# Display-Board_Rack-PDU_3_0.net
KiCad netlist of a schematic drawn in EAGLE
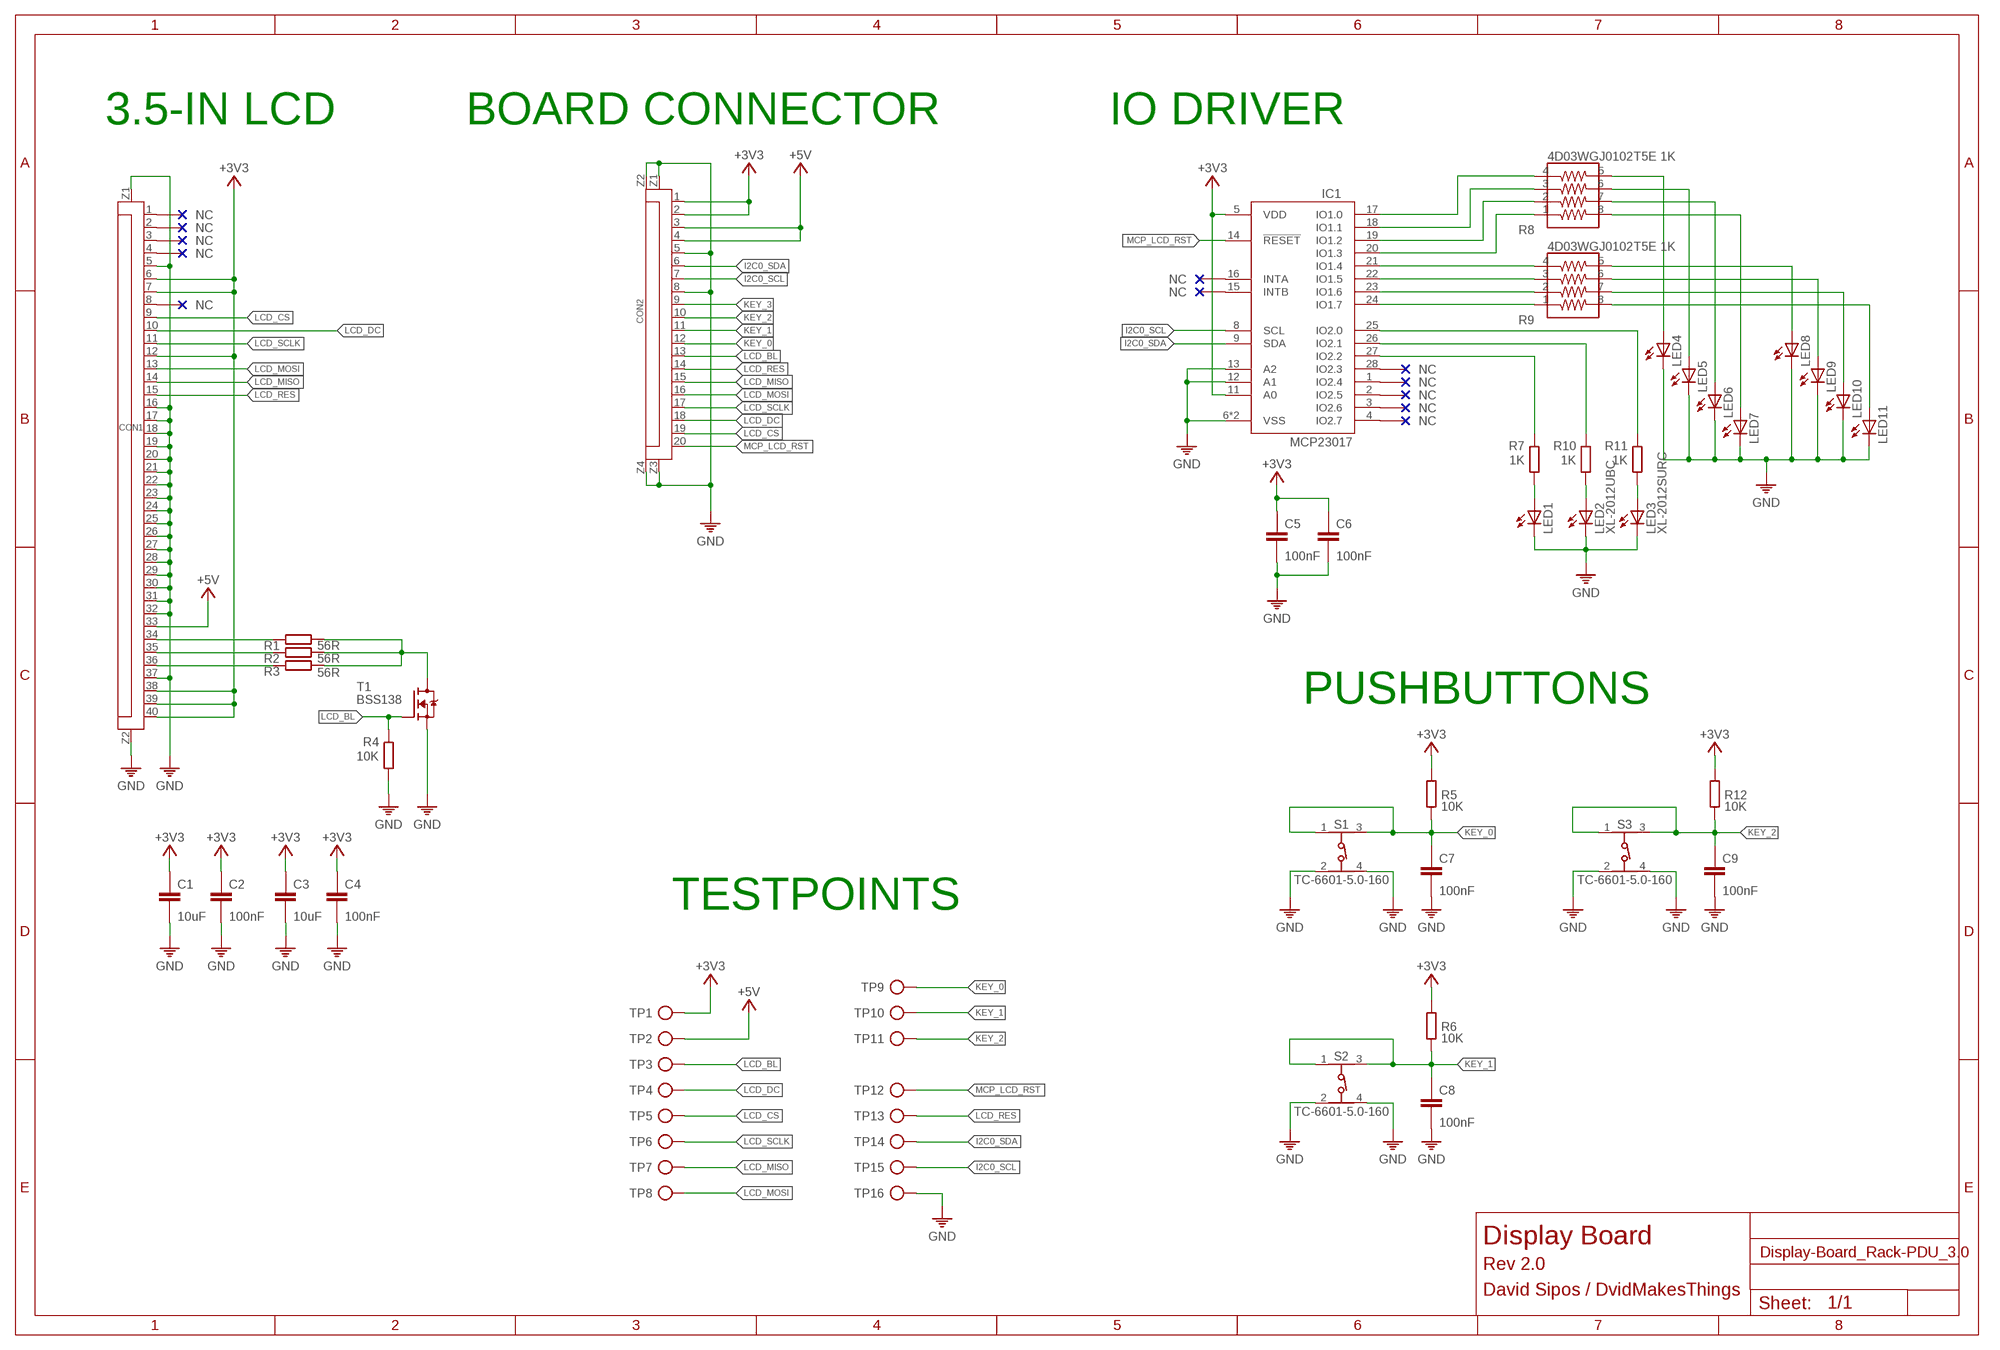
[diagram p0: schematic, sheet 1]

(export (version "E")
  (design (tool "Eeschema 10.0.6"))
  (components
    (comp (ref "C1")
      (value "10uF")
      (footprint "eagle-import:C0402")
      (libsource (lib "eagle-import") (part "C-0402"))
    )
    (comp (ref "C2")
      (value "100nF")
      (footprint "eagle-import:C0402")
      (libsource (lib "eagle-import") (part "C-0402"))
    )
    (comp (ref "C3")
      (value "10uF")
      (footprint "eagle-import:C0402")
      (libsource (lib "eagle-import") (part "C-0402"))
    )
    (comp (ref "C4")
      (value "100nF")
      (footprint "eagle-import:C0402")
      (libsource (lib "eagle-import") (part "C-0402"))
    )
    (comp (ref "C5")
      (value "100nF")
      (footprint "eagle-import:C0402")
      (libsource (lib "eagle-import") (part "C-0402"))
    )
    (comp (ref "C6")
      (value "100nF")
      (footprint "eagle-import:C0402")
      (libsource (lib "eagle-import") (part "C-0402"))
    )
    (comp (ref "C7")
      (value "100nF")
      (footprint "eagle-import:C0402")
      (libsource (lib "eagle-import") (part "C-0402"))
    )
    (comp (ref "C8")
      (value "100nF")
      (footprint "eagle-import:C0402")
      (libsource (lib "eagle-import") (part "C-0402"))
    )
    (comp (ref "C9")
      (value "100nF")
      (footprint "eagle-import:C0402")
      (libsource (lib "eagle-import") (part "C-0402"))
    )
    (comp (ref "CON1")
      (value "FPC40-HD")
      (footprint "eagle-import:FPC40_3.5TFT")
      (libsource (lib "eagle-import") (part "FPC40-HD"))
    )
    (comp (ref "CON2")
      (value "FPC20-H")
      (footprint "eagle-import:FPC20")
      (libsource (lib "eagle-import") (part "FPC20-H"))
    )
    (comp (ref "IC1")
      (value "MCP23017-E/ML")
      (footprint "eagle-import:QFN28[6X6]ML")
      (libsource (lib "eagle-import") (part "MCP23017-E/ML"))
    )
    (comp (ref "LED1")
      (value "LEDCHIP-LED0805")
      (footprint "eagle-import:CHIP-LED0805")
      (libsource (lib "eagle-import") (part "LEDCHIP-LED0805"))
    )
    (comp (ref "LED2")
      (value "XL-2012UBC")
      (footprint "eagle-import:CHIP-LED0805")
      (libsource (lib "eagle-import") (part "LEDCHIP-LED0805"))
    )
    (comp (ref "LED3")
      (value "XL-2012SURC")
      (footprint "eagle-import:CHIP-LED0805")
      (libsource (lib "eagle-import") (part "LEDCHIP-LED0805"))
    )
    (comp (ref "LED4")
      (value "LEDCHIP-LED0805")
      (footprint "eagle-import:CHIP-LED0805")
      (libsource (lib "eagle-import") (part "LEDCHIP-LED0805"))
    )
    (comp (ref "LED5")
      (value "LEDCHIP-LED0805")
      (footprint "eagle-import:CHIP-LED0805")
      (libsource (lib "eagle-import") (part "LEDCHIP-LED0805"))
    )
    (comp (ref "LED6")
      (value "LEDCHIP-LED0805")
      (footprint "eagle-import:CHIP-LED0805")
      (libsource (lib "eagle-import") (part "LEDCHIP-LED0805"))
    )
    (comp (ref "LED7")
      (value "LEDCHIP-LED0805")
      (footprint "eagle-import:CHIP-LED0805")
      (libsource (lib "eagle-import") (part "LEDCHIP-LED0805"))
    )
    (comp (ref "LED8")
      (value "LEDCHIP-LED0805")
      (footprint "eagle-import:CHIP-LED0805")
      (libsource (lib "eagle-import") (part "LEDCHIP-LED0805"))
    )
    (comp (ref "LED9")
      (value "LEDCHIP-LED0805")
      (footprint "eagle-import:CHIP-LED0805")
      (libsource (lib "eagle-import") (part "LEDCHIP-LED0805"))
    )
    (comp (ref "LED10")
      (value "LEDCHIP-LED0805")
      (footprint "eagle-import:CHIP-LED0805")
      (libsource (lib "eagle-import") (part "LEDCHIP-LED0805"))
    )
    (comp (ref "LED11")
      (value "LEDCHIP-LED0805")
      (footprint "eagle-import:CHIP-LED0805")
      (libsource (lib "eagle-import") (part "LEDCHIP-LED0805"))
    )
    (comp (ref "R1")
      (value "56R")
      (footprint "eagle-import:0402")
      (libsource (lib "eagle-import") (part "R0402"))
    )
    (comp (ref "R2")
      (value "56R")
      (footprint "eagle-import:0402")
      (libsource (lib "eagle-import") (part "R0402"))
    )
    (comp (ref "R3")
      (value "56R")
      (footprint "eagle-import:0402")
      (libsource (lib "eagle-import") (part "R0402"))
    )
    (comp (ref "R4")
      (value "10K")
      (footprint "eagle-import:0402")
      (libsource (lib "eagle-import") (part "R0402"))
    )
    (comp (ref "R5")
      (value "10K")
      (footprint "eagle-import:0402")
      (libsource (lib "eagle-import") (part "R0402"))
    )
    (comp (ref "R6")
      (value "10K")
      (footprint "eagle-import:0402")
      (libsource (lib "eagle-import") (part "R0402"))
    )
    (comp (ref "R7")
      (value "1K")
      (footprint "eagle-import:0402")
      (libsource (lib "eagle-import") (part "R0402"))
    )
    (comp (ref "R8")
      (value "4D03WGJ0102T5E 1K")
      (footprint "eagle-import:742C083103JP")
      (fields
        (field (name "MANUFACTURER") "CTS Resistor Products")
        (field (name "MPN") "742C083103JP")
        (field (name "CREATED_BY") "PCBLayout.com")
      )
      (libsource (lib "eagle-import") (part "742C083103JP"))
    )
    (comp (ref "R9")
      (value "4D03WGJ0102T5E 1K")
      (footprint "eagle-import:742C083103JP")
      (fields
        (field (name "MANUFACTURER") "CTS Resistor Products")
        (field (name "MPN") "742C083103JP")
        (field (name "CREATED_BY") "PCBLayout.com")
      )
      (libsource (lib "eagle-import") (part "742C083103JP"))
    )
    (comp (ref "R10")
      (value "1K")
      (footprint "eagle-import:0402")
      (libsource (lib "eagle-import") (part "R0402"))
    )
    (comp (ref "R11")
      (value "1K")
      (footprint "eagle-import:0402")
      (libsource (lib "eagle-import") (part "R0402"))
    )
    (comp (ref "R12")
      (value "10K")
      (footprint "eagle-import:0402")
      (libsource (lib "eagle-import") (part "R0402"))
    )
    (comp (ref "S1")
      (value "TC-6601-5.0-160")
      (footprint "eagle-import:430182043816")
      (libsource (lib "eagle-import") (part "430182043816"))
    )
    (comp (ref "S2")
      (value "TC-6601-5.0-160")
      (footprint "eagle-import:430182043816")
      (libsource (lib "eagle-import") (part "430182043816"))
    )
    (comp (ref "S3")
      (value "TC-6601-5.0-160")
      (footprint "eagle-import:430182043816")
      (libsource (lib "eagle-import") (part "430182043816"))
    )
    (comp (ref "T1")
      (value "BSS138")
      (footprint "eagle-import:SOT23")
      (libsource (lib "eagle-import") (part "BSS138"))
    )
    (comp (ref "TP1") (value "TP") (footprint "eagle-import:TP") (libsource (lib "eagle-import") (part "TP")))
    (comp (ref "TP2") (value "TP") (footprint "eagle-import:TP") (libsource (lib "eagle-import") (part "TP")))
    (comp (ref "TP3") (value "TP") (footprint "eagle-import:TP") (libsource (lib "eagle-import") (part "TP")))
    (comp (ref "TP4") (value "TP") (footprint "eagle-import:TP") (libsource (lib "eagle-import") (part "TP")))
    (comp (ref "TP5") (value "TP") (footprint "eagle-import:TP") (libsource (lib "eagle-import") (part "TP")))
    (comp (ref "TP6") (value "TP") (footprint "eagle-import:TP") (libsource (lib "eagle-import") (part "TP")))
    (comp (ref "TP7") (value "TP") (footprint "eagle-import:TP") (libsource (lib "eagle-import") (part "TP")))
    (comp (ref "TP8") (value "TP") (footprint "eagle-import:TP") (libsource (lib "eagle-import") (part "TP")))
    (comp (ref "TP9") (value "TP") (footprint "eagle-import:TP") (libsource (lib "eagle-import") (part "TP")))
    (comp (ref "TP10")
      (value "TP")
      (footprint "eagle-import:TP")
      (libsource (lib "eagle-import") (part "TP"))
    )
    (comp (ref "TP11")
      (value "TP")
      (footprint "eagle-import:TP")
      (libsource (lib "eagle-import") (part "TP"))
    )
    (comp (ref "TP12")
      (value "TP")
      (footprint "eagle-import:TP")
      (libsource (lib "eagle-import") (part "TP"))
    )
    (comp (ref "TP13")
      (value "TP")
      (footprint "eagle-import:TP")
      (libsource (lib "eagle-import") (part "TP"))
    )
    (comp (ref "TP14")
      (value "TP")
      (footprint "eagle-import:TP")
      (libsource (lib "eagle-import") (part "TP"))
    )
    (comp (ref "TP15")
      (value "TP")
      (footprint "eagle-import:TP")
      (libsource (lib "eagle-import") (part "TP"))
    )
    (comp (ref "TP16")
      (value "TP")
      (footprint "eagle-import:TP")
      (libsource (lib "eagle-import") (part "TP"))
    )
  )
  (nets
    (net (code "1") (name "+3V3") (class "Default")
      (node (ref "C1") (pin "1") (pinfunction "1_1") (pintype "passive"))
      (node (ref "C2") (pin "1") (pinfunction "1_1") (pintype "passive"))
      (node (ref "C3") (pin "1") (pinfunction "1_1") (pintype "passive"))
      (node (ref "C4") (pin "1") (pinfunction "1_1") (pintype "passive"))
      (node (ref "C5") (pin "1") (pinfunction "1_1") (pintype "passive"))
      (node (ref "C6") (pin "1") (pinfunction "1_1") (pintype "passive"))
      (node (ref "CON1") (pin "12") (pinfunction "12_12") (pintype "bidirectional"))
      (node (ref "CON1") (pin "38") (pinfunction "38_38") (pintype "bidirectional"))
      (node (ref "CON1") (pin "39") (pinfunction "39_39") (pintype "bidirectional"))
      (node (ref "CON1") (pin "40") (pinfunction "40_40") (pintype "bidirectional"))
      (node (ref "CON1") (pin "6") (pinfunction "6_6") (pintype "bidirectional"))
      (node (ref "CON1") (pin "7") (pinfunction "7_7") (pintype "bidirectional"))
      (node (ref "CON2") (pin "1") (pinfunction "1_1") (pintype "bidirectional"))
      (node (ref "CON2") (pin "2") (pinfunction "2_2") (pintype "bidirectional"))
      (node (ref "IC1") (pin "11") (pinfunction "A0_11") (pintype "bidirectional"))
      (node (ref "IC1") (pin "5") (pinfunction "VDD_5") (pintype "bidirectional"))
      (node (ref "R12") (pin "1") (pinfunction "1_1") (pintype "passive"))
      (node (ref "R5") (pin "1") (pinfunction "1_1") (pintype "passive"))
      (node (ref "R6") (pin "1") (pinfunction "1_1") (pintype "passive"))
      (node (ref "TP1") (pin "TP") (pinfunction "P$1_TP") (pintype "bidirectional"))
    )
    (net (code "2") (name "+5V") (class "Default")
      (node (ref "CON1") (pin "33") (pinfunction "33_33") (pintype "bidirectional"))
      (node (ref "CON2") (pin "3") (pinfunction "3_3") (pintype "bidirectional"))
      (node (ref "CON2") (pin "4") (pinfunction "4_4") (pintype "bidirectional"))
      (node (ref "TP2") (pin "TP") (pinfunction "P$1_TP") (pintype "bidirectional"))
    )
    (net (code "3") (name "GND") (class "Default")
      (node (ref "C1") (pin "2") (pinfunction "2_2") (pintype "passive"))
      (node (ref "C2") (pin "2") (pinfunction "2_2") (pintype "passive"))
      (node (ref "C3") (pin "2") (pinfunction "2_2") (pintype "passive"))
      (node (ref "C4") (pin "2") (pinfunction "2_2") (pintype "passive"))
      (node (ref "C5") (pin "2") (pinfunction "2_2") (pintype "passive"))
      (node (ref "C6") (pin "2") (pinfunction "2_2") (pintype "passive"))
      (node (ref "C7") (pin "2") (pinfunction "2_2") (pintype "passive"))
      (node (ref "C8") (pin "2") (pinfunction "2_2") (pintype "passive"))
      (node (ref "C9") (pin "2") (pinfunction "2_2") (pintype "passive"))
      (node (ref "CON1") (pin "16") (pinfunction "16_16") (pintype "bidirectional"))
      (node (ref "CON1") (pin "17") (pinfunction "17_17") (pintype "bidirectional"))
      (node (ref "CON1") (pin "18") (pinfunction "18_18") (pintype "bidirectional"))
      (node (ref "CON1") (pin "19") (pinfunction "19_19") (pintype "bidirectional"))
      (node (ref "CON1") (pin "20") (pinfunction "20_20") (pintype "bidirectional"))
      (node (ref "CON1") (pin "21") (pinfunction "21_21") (pintype "bidirectional"))
      (node (ref "CON1") (pin "22") (pinfunction "22_22") (pintype "bidirectional"))
      (node (ref "CON1") (pin "23") (pinfunction "23_23") (pintype "bidirectional"))
      (node (ref "CON1") (pin "24") (pinfunction "24_24") (pintype "bidirectional"))
      (node (ref "CON1") (pin "25") (pinfunction "25_25") (pintype "bidirectional"))
      (node (ref "CON1") (pin "26") (pinfunction "26_26") (pintype "bidirectional"))
      (node (ref "CON1") (pin "27") (pinfunction "27_27") (pintype "bidirectional"))
      (node (ref "CON1") (pin "28") (pinfunction "28_28") (pintype "bidirectional"))
      (node (ref "CON1") (pin "29") (pinfunction "29_29") (pintype "bidirectional"))
      (node (ref "CON1") (pin "30") (pinfunction "30_30") (pintype "bidirectional"))
      (node (ref "CON1") (pin "31") (pinfunction "31_31") (pintype "bidirectional"))
      (node (ref "CON1") (pin "32") (pinfunction "32_32") (pintype "bidirectional"))
      (node (ref "CON1") (pin "37") (pinfunction "37_37") (pintype "bidirectional"))
      (node (ref "CON1") (pin "5") (pinfunction "5_5") (pintype "bidirectional"))
      (node (ref "CON1") (pin "Z1") (pinfunction "Z1_Z1") (pintype "bidirectional"))
      (node (ref "CON1") (pin "Z2") (pinfunction "Z2_Z2") (pintype "bidirectional"))
      (node (ref "CON2") (pin "5") (pinfunction "5_5") (pintype "bidirectional"))
      (node (ref "CON2") (pin "8") (pinfunction "8_8") (pintype "bidirectional"))
      (node (ref "CON2") (pin "Z1") (pinfunction "Z1_Z1") (pintype "bidirectional"))
      (node (ref "CON2") (pin "Z2") (pinfunction "Z2_Z2") (pintype "bidirectional"))
      (node (ref "CON2") (pin "Z3") (pinfunction "Z3_Z3") (pintype "bidirectional"))
      (node (ref "CON2") (pin "Z4") (pinfunction "Z4_Z4") (pintype "bidirectional"))
      (node (ref "IC1") (pin "12") (pinfunction "A1_12") (pintype "bidirectional"))
      (node (ref "IC1") (pin "13") (pinfunction "A2_13") (pintype "bidirectional"))
      (node (ref "IC1") (pin "6") (pinfunction "VSS_6") (pintype "bidirectional"))
      (node (ref "IC1") (pin "PAD") (pinfunction "VSS_PAD") (pintype "bidirectional"))
      (node (ref "LED1") (pin "C") (pinfunction "C_C") (pintype "passive"))
      (node (ref "LED10") (pin "C") (pinfunction "C_C") (pintype "passive"))
      (node (ref "LED11") (pin "C") (pinfunction "C_C") (pintype "passive"))
      (node (ref "LED2") (pin "C") (pinfunction "C_C") (pintype "passive"))
      (node (ref "LED3") (pin "C") (pinfunction "C_C") (pintype "passive"))
      (node (ref "LED4") (pin "C") (pinfunction "C_C") (pintype "passive"))
      (node (ref "LED5") (pin "C") (pinfunction "C_C") (pintype "passive"))
      (node (ref "LED6") (pin "C") (pinfunction "C_C") (pintype "passive"))
      (node (ref "LED7") (pin "C") (pinfunction "C_C") (pintype "passive"))
      (node (ref "LED8") (pin "C") (pinfunction "C_C") (pintype "passive"))
      (node (ref "LED9") (pin "C") (pinfunction "C_C") (pintype "passive"))
      (node (ref "R4") (pin "2") (pinfunction "2_2") (pintype "passive"))
      (node (ref "S1") (pin "2") (pinfunction "2_2") (pintype "passive"))
      (node (ref "S1") (pin "4") (pinfunction "4_4") (pintype "passive"))
      (node (ref "S2") (pin "2") (pinfunction "2_2") (pintype "passive"))
      (node (ref "S2") (pin "4") (pinfunction "4_4") (pintype "passive"))
      (node (ref "S3") (pin "2") (pinfunction "2_2") (pintype "passive"))
      (node (ref "S3") (pin "4") (pinfunction "4_4") (pintype "passive"))
      (node (ref "T1") (pin "2") (pinfunction "S_2") (pintype "passive"))
      (node (ref "TP16") (pin "TP") (pinfunction "P$1_TP") (pintype "bidirectional"))
    )
    (net (code "4") (name "I2C0_SCL") (class "Default")
      (node (ref "CON2") (pin "7") (pinfunction "7_7") (pintype "bidirectional"))
      (node (ref "IC1") (pin "8") (pinfunction "SCL_8") (pintype "bidirectional"))
      (node (ref "TP15") (pin "TP") (pinfunction "P$1_TP") (pintype "bidirectional"))
    )
    (net (code "5") (name "I2C0_SDA") (class "Default")
      (node (ref "CON2") (pin "6") (pinfunction "6_6") (pintype "bidirectional"))
      (node (ref "IC1") (pin "9") (pinfunction "SDA_9") (pintype "bidirectional"))
      (node (ref "TP14") (pin "TP") (pinfunction "P$1_TP") (pintype "bidirectional"))
    )
    (net (code "6") (name "KEY_0") (class "Default")
      (node (ref "C7") (pin "1") (pinfunction "1_1") (pintype "passive"))
      (node (ref "CON2") (pin "12") (pinfunction "12_12") (pintype "bidirectional"))
      (node (ref "R5") (pin "2") (pinfunction "2_2") (pintype "passive"))
      (node (ref "S1") (pin "1") (pinfunction "1_1") (pintype "passive"))
      (node (ref "S1") (pin "3") (pinfunction "3_3") (pintype "passive"))
      (node (ref "TP9") (pin "TP") (pinfunction "P$1_TP") (pintype "bidirectional"))
    )
    (net (code "7") (name "KEY_1") (class "Default")
      (node (ref "C8") (pin "1") (pinfunction "1_1") (pintype "passive"))
      (node (ref "CON2") (pin "11") (pinfunction "11_11") (pintype "bidirectional"))
      (node (ref "R6") (pin "2") (pinfunction "2_2") (pintype "passive"))
      (node (ref "S2") (pin "1") (pinfunction "1_1") (pintype "passive"))
      (node (ref "S2") (pin "3") (pinfunction "3_3") (pintype "passive"))
      (node (ref "TP10") (pin "TP") (pinfunction "P$1_TP") (pintype "bidirectional"))
    )
    (net (code "8") (name "KEY_2") (class "Default")
      (node (ref "C9") (pin "1") (pinfunction "1_1") (pintype "passive"))
      (node (ref "CON2") (pin "10") (pinfunction "10_10") (pintype "bidirectional"))
      (node (ref "R12") (pin "2") (pinfunction "2_2") (pintype "passive"))
      (node (ref "S3") (pin "1") (pinfunction "1_1") (pintype "passive"))
      (node (ref "S3") (pin "3") (pinfunction "3_3") (pintype "passive"))
      (node (ref "TP11") (pin "TP") (pinfunction "P$1_TP") (pintype "bidirectional"))
    )
    (net (code "9") (name "KEY_3") (class "Default")
      (node (ref "CON2") (pin "9") (pinfunction "9_9") (pintype "bidirectional"))
    )
    (net (code "10") (name "LCD_BL") (class "Default")
      (node (ref "CON2") (pin "13") (pinfunction "13_13") (pintype "bidirectional"))
      (node (ref "R4") (pin "1") (pinfunction "1_1") (pintype "passive"))
      (node (ref "T1") (pin "1") (pinfunction "G_1") (pintype "passive"))
      (node (ref "TP3") (pin "TP") (pinfunction "P$1_TP") (pintype "bidirectional"))
    )
    (net (code "11") (name "LCD_CS") (class "Default")
      (node (ref "CON1") (pin "9") (pinfunction "9_9") (pintype "bidirectional"))
      (node (ref "CON2") (pin "19") (pinfunction "19_19") (pintype "bidirectional"))
      (node (ref "TP5") (pin "TP") (pinfunction "P$1_TP") (pintype "bidirectional"))
    )
    (net (code "12") (name "LCD_DC") (class "Default")
      (node (ref "CON1") (pin "10") (pinfunction "10_10") (pintype "bidirectional"))
      (node (ref "CON2") (pin "18") (pinfunction "18_18") (pintype "bidirectional"))
      (node (ref "TP4") (pin "TP") (pinfunction "P$1_TP") (pintype "bidirectional"))
    )
    (net (code "13") (name "LCD_MISO") (class "Default")
      (node (ref "CON1") (pin "14") (pinfunction "14_14") (pintype "bidirectional"))
      (node (ref "CON2") (pin "15") (pinfunction "15_15") (pintype "bidirectional"))
      (node (ref "TP7") (pin "TP") (pinfunction "P$1_TP") (pintype "bidirectional"))
    )
    (net (code "14") (name "LCD_MOSI") (class "Default")
      (node (ref "CON1") (pin "13") (pinfunction "13_13") (pintype "bidirectional"))
      (node (ref "CON2") (pin "16") (pinfunction "16_16") (pintype "bidirectional"))
      (node (ref "TP8") (pin "TP") (pinfunction "P$1_TP") (pintype "bidirectional"))
    )
    (net (code "15") (name "LCD_RES") (class "Default")
      (node (ref "CON1") (pin "15") (pinfunction "15_15") (pintype "bidirectional"))
      (node (ref "CON2") (pin "14") (pinfunction "14_14") (pintype "bidirectional"))
      (node (ref "TP13") (pin "TP") (pinfunction "P$1_TP") (pintype "bidirectional"))
    )
    (net (code "16") (name "LCD_SCLK") (class "Default")
      (node (ref "CON1") (pin "11") (pinfunction "11_11") (pintype "bidirectional"))
      (node (ref "CON2") (pin "17") (pinfunction "17_17") (pintype "bidirectional"))
      (node (ref "TP6") (pin "TP") (pinfunction "P$1_TP") (pintype "bidirectional"))
    )
    (net (code "17") (name "MCP_LCD_RST") (class "Default")
      (node (ref "CON2") (pin "20") (pinfunction "20_20") (pintype "bidirectional"))
      (node (ref "IC1") (pin "14") (pinfunction "~{RESET}_14") (pintype "bidirectional"))
      (node (ref "TP12") (pin "TP") (pinfunction "P$1_TP") (pintype "bidirectional"))
    )
    (net (code "18") (name "Net-(CON1-Pad34)") (class "Default")
      (node (ref "CON1") (pin "34") (pinfunction "34_34") (pintype "bidirectional"))
      (node (ref "R1") (pin "2") (pinfunction "2_2") (pintype "passive"))
    )
    (net (code "19") (name "Net-(CON1-Pad35)") (class "Default")
      (node (ref "CON1") (pin "35") (pinfunction "35_35") (pintype "bidirectional"))
      (node (ref "R2") (pin "2") (pinfunction "2_2") (pintype "passive"))
    )
    (net (code "20") (name "Net-(CON1-Pad36)") (class "Default")
      (node (ref "CON1") (pin "36") (pinfunction "36_36") (pintype "bidirectional"))
      (node (ref "R3") (pin "2") (pinfunction "2_2") (pintype "passive"))
    )
    (net (code "21") (name "Net-(IC1-IO1.0)") (class "Default")
      (node (ref "IC1") (pin "17") (pinfunction "IO1.0_17") (pintype "bidirectional"))
      (node (ref "R8") (pin "4") (pinfunction "4_4") (pintype "passive"))
    )
    (net (code "22") (name "Net-(IC1-IO1.1)") (class "Default")
      (node (ref "IC1") (pin "18") (pinfunction "IO1.1_18") (pintype "bidirectional"))
      (node (ref "R8") (pin "3") (pinfunction "3_3") (pintype "passive"))
    )
    (net (code "23") (name "Net-(IC1-IO1.2)") (class "Default")
      (node (ref "IC1") (pin "19") (pinfunction "IO1.2_19") (pintype "bidirectional"))
      (node (ref "R8") (pin "2") (pinfunction "2_2") (pintype "passive"))
    )
    (net (code "24") (name "Net-(IC1-IO1.3)") (class "Default")
      (node (ref "IC1") (pin "20") (pinfunction "IO1.3_20") (pintype "bidirectional"))
      (node (ref "R8") (pin "1") (pinfunction "1_1") (pintype "passive"))
    )
    (net (code "25") (name "Net-(IC1-IO1.4)") (class "Default")
      (node (ref "IC1") (pin "21") (pinfunction "IO1.4_21") (pintype "bidirectional"))
      (node (ref "R9") (pin "4") (pinfunction "4_4") (pintype "passive"))
    )
    (net (code "26") (name "Net-(IC1-IO1.5)") (class "Default")
      (node (ref "IC1") (pin "22") (pinfunction "IO1.5_22") (pintype "bidirectional"))
      (node (ref "R9") (pin "3") (pinfunction "3_3") (pintype "passive"))
    )
    (net (code "27") (name "Net-(IC1-IO1.6)") (class "Default")
      (node (ref "IC1") (pin "23") (pinfunction "IO1.6_23") (pintype "bidirectional"))
      (node (ref "R9") (pin "2") (pinfunction "2_2") (pintype "passive"))
    )
    (net (code "28") (name "Net-(IC1-IO1.7)") (class "Default")
      (node (ref "IC1") (pin "24") (pinfunction "IO1.7_24") (pintype "bidirectional"))
      (node (ref "R9") (pin "1") (pinfunction "1_1") (pintype "passive"))
    )
    (net (code "29") (name "Net-(IC1-IO2.0)") (class "Default")
      (node (ref "IC1") (pin "25") (pinfunction "IO2.0_25") (pintype "bidirectional"))
      (node (ref "R11") (pin "1") (pinfunction "1_1") (pintype "passive"))
    )
    (net (code "30") (name "Net-(IC1-IO2.1)") (class "Default")
      (node (ref "IC1") (pin "26") (pinfunction "IO2.1_26") (pintype "bidirectional"))
      (node (ref "R10") (pin "1") (pinfunction "1_1") (pintype "passive"))
    )
    (net (code "31") (name "Net-(IC1-IO2.2)") (class "Default")
      (node (ref "IC1") (pin "27") (pinfunction "IO2.2_27") (pintype "bidirectional"))
      (node (ref "R7") (pin "1") (pinfunction "1_1") (pintype "passive"))
    )
    (net (code "32") (name "Net-(LED1-PadA)") (class "Default")
      (node (ref "LED1") (pin "A") (pinfunction "A_A") (pintype "passive"))
      (node (ref "R7") (pin "2") (pinfunction "2_2") (pintype "passive"))
    )
    (net (code "33") (name "Net-(LED2-PadA)") (class "Default")
      (node (ref "LED2") (pin "A") (pinfunction "A_A") (pintype "passive"))
      (node (ref "R10") (pin "2") (pinfunction "2_2") (pintype "passive"))
    )
    (net (code "34") (name "Net-(LED3-PadA)") (class "Default")
      (node (ref "LED3") (pin "A") (pinfunction "A_A") (pintype "passive"))
      (node (ref "R11") (pin "2") (pinfunction "2_2") (pintype "passive"))
    )
    (net (code "35") (name "Net-(LED4-PadA)") (class "Default")
      (node (ref "LED4") (pin "A") (pinfunction "A_A") (pintype "passive"))
      (node (ref "R8") (pin "5") (pinfunction "5_5") (pintype "passive"))
    )
    (net (code "36") (name "Net-(LED5-PadA)") (class "Default")
      (node (ref "LED5") (pin "A") (pinfunction "A_A") (pintype "passive"))
      (node (ref "R8") (pin "6") (pinfunction "6_6") (pintype "passive"))
    )
    (net (code "37") (name "Net-(LED6-PadA)") (class "Default")
      (node (ref "LED6") (pin "A") (pinfunction "A_A") (pintype "passive"))
      (node (ref "R8") (pin "7") (pinfunction "7_7") (pintype "passive"))
    )
    (net (code "38") (name "Net-(LED7-PadA)") (class "Default")
      (node (ref "LED7") (pin "A") (pinfunction "A_A") (pintype "passive"))
      (node (ref "R8") (pin "8") (pinfunction "8_8") (pintype "passive"))
    )
    (net (code "39") (name "Net-(LED8-PadA)") (class "Default")
      (node (ref "LED8") (pin "A") (pinfunction "A_A") (pintype "passive"))
      (node (ref "R9") (pin "5") (pinfunction "5_5") (pintype "passive"))
    )
    (net (code "40") (name "Net-(LED9-PadA)") (class "Default")
      (node (ref "LED9") (pin "A") (pinfunction "A_A") (pintype "passive"))
      (node (ref "R9") (pin "6") (pinfunction "6_6") (pintype "passive"))
    )
    (net (code "41") (name "Net-(LED10-PadA)") (class "Default")
      (node (ref "LED10") (pin "A") (pinfunction "A_A") (pintype "passive"))
      (node (ref "R9") (pin "7") (pinfunction "7_7") (pintype "passive"))
    )
    (net (code "42") (name "Net-(LED11-PadA)") (class "Default")
      (node (ref "LED11") (pin "A") (pinfunction "A_A") (pintype "passive"))
      (node (ref "R9") (pin "8") (pinfunction "8_8") (pintype "passive"))
    )
    (net (code "43") (name "Net-(T1-D)") (class "Default")
      (node (ref "R1") (pin "1") (pinfunction "1_1") (pintype "passive"))
      (node (ref "R2") (pin "1") (pinfunction "1_1") (pintype "passive"))
      (node (ref "R3") (pin "1") (pinfunction "1_1") (pintype "passive"))
      (node (ref "T1") (pin "3") (pinfunction "D_3") (pintype "passive"))
    )
    (net (code "44") (name "unconnected-(CON1-Pad1)") (class "Default")
      (node (ref "CON1") (pin "1") (pinfunction "1_1") (pintype "bidirectional"))
    )
    (net (code "45") (name "unconnected-(CON1-Pad2)") (class "Default")
      (node (ref "CON1") (pin "2") (pinfunction "2_2") (pintype "bidirectional"))
    )
    (net (code "46") (name "unconnected-(CON1-Pad3)") (class "Default")
      (node (ref "CON1") (pin "3") (pinfunction "3_3") (pintype "bidirectional"))
    )
    (net (code "47") (name "unconnected-(CON1-Pad4)") (class "Default")
      (node (ref "CON1") (pin "4") (pinfunction "4_4") (pintype "bidirectional"))
    )
    (net (code "48") (name "unconnected-(CON1-Pad8)") (class "Default")
      (node (ref "CON1") (pin "8") (pinfunction "8_8") (pintype "bidirectional"))
    )
    (net (code "49") (name "unconnected-(IC1-INTA-Pad16)") (class "Default")
      (node (ref "IC1") (pin "16") (pinfunction "INTA_16") (pintype "bidirectional"))
    )
    (net (code "50") (name "unconnected-(IC1-INTB-Pad15)") (class "Default")
      (node (ref "IC1") (pin "15") (pinfunction "INTB_15") (pintype "bidirectional"))
    )
    (net (code "51") (name "unconnected-(IC1-IO2.3-Pad28)") (class "Default")
      (node (ref "IC1") (pin "28") (pinfunction "IO2.3_28") (pintype "bidirectional"))
    )
    (net (code "52") (name "unconnected-(IC1-IO2.4-Pad1)") (class "Default")
      (node (ref "IC1") (pin "1") (pinfunction "IO2.4_1") (pintype "bidirectional"))
    )
    (net (code "53") (name "unconnected-(IC1-IO2.5-Pad2)") (class "Default")
      (node (ref "IC1") (pin "2") (pinfunction "IO2.5_2") (pintype "bidirectional"))
    )
    (net (code "54") (name "unconnected-(IC1-IO2.6-Pad3)") (class "Default")
      (node (ref "IC1") (pin "3") (pinfunction "IO2.6_3") (pintype "bidirectional"))
    )
    (net (code "55") (name "unconnected-(IC1-IO2.7-Pad4)") (class "Default")
      (node (ref "IC1") (pin "4") (pinfunction "IO2.7_4") (pintype "bidirectional"))
    )
  )
)
